# Grill_simple_bord.net
KiCad netlist of a schematic drawn in EAGLE
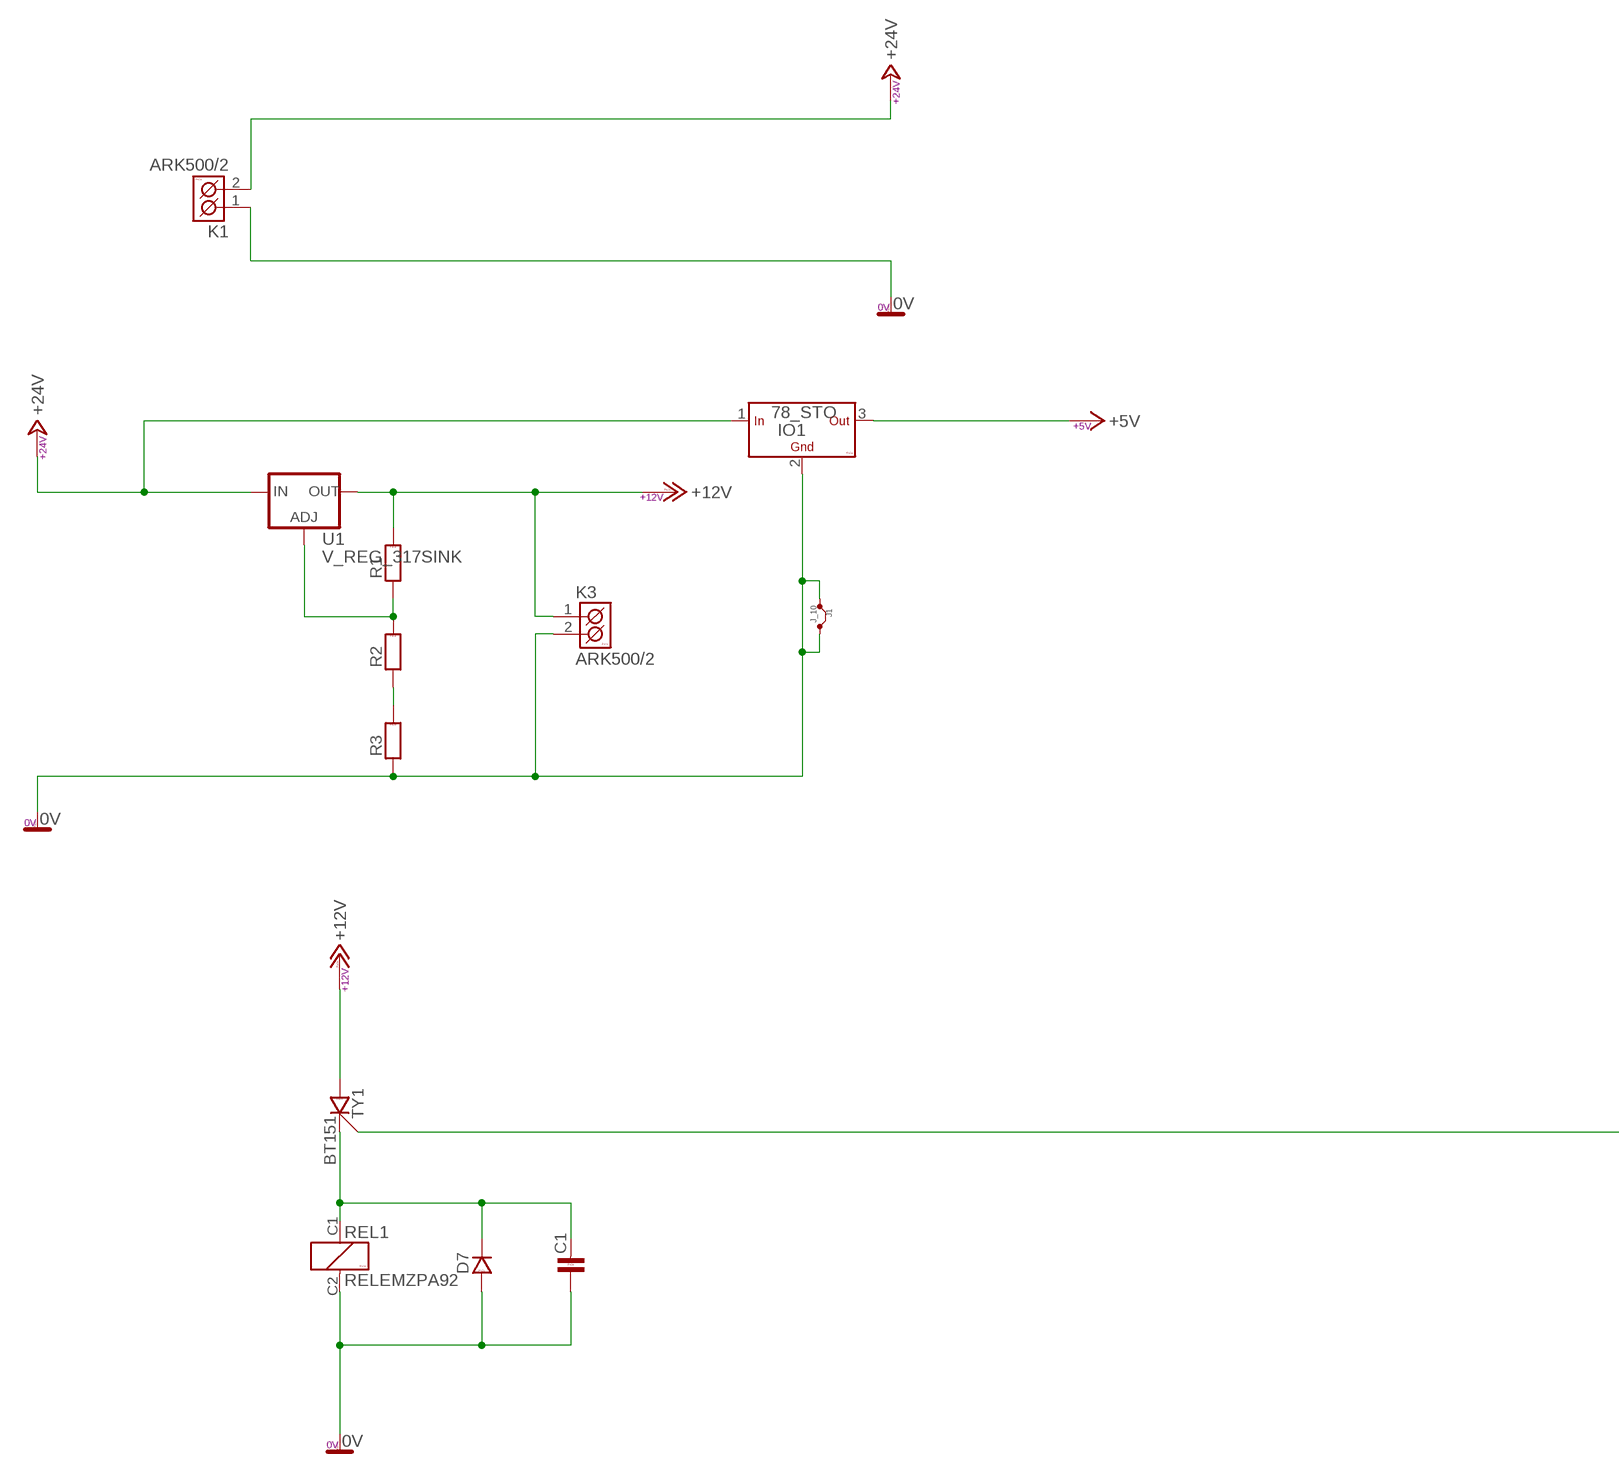
[diagram p0: schematic, sheet 1, part 1 of 2]
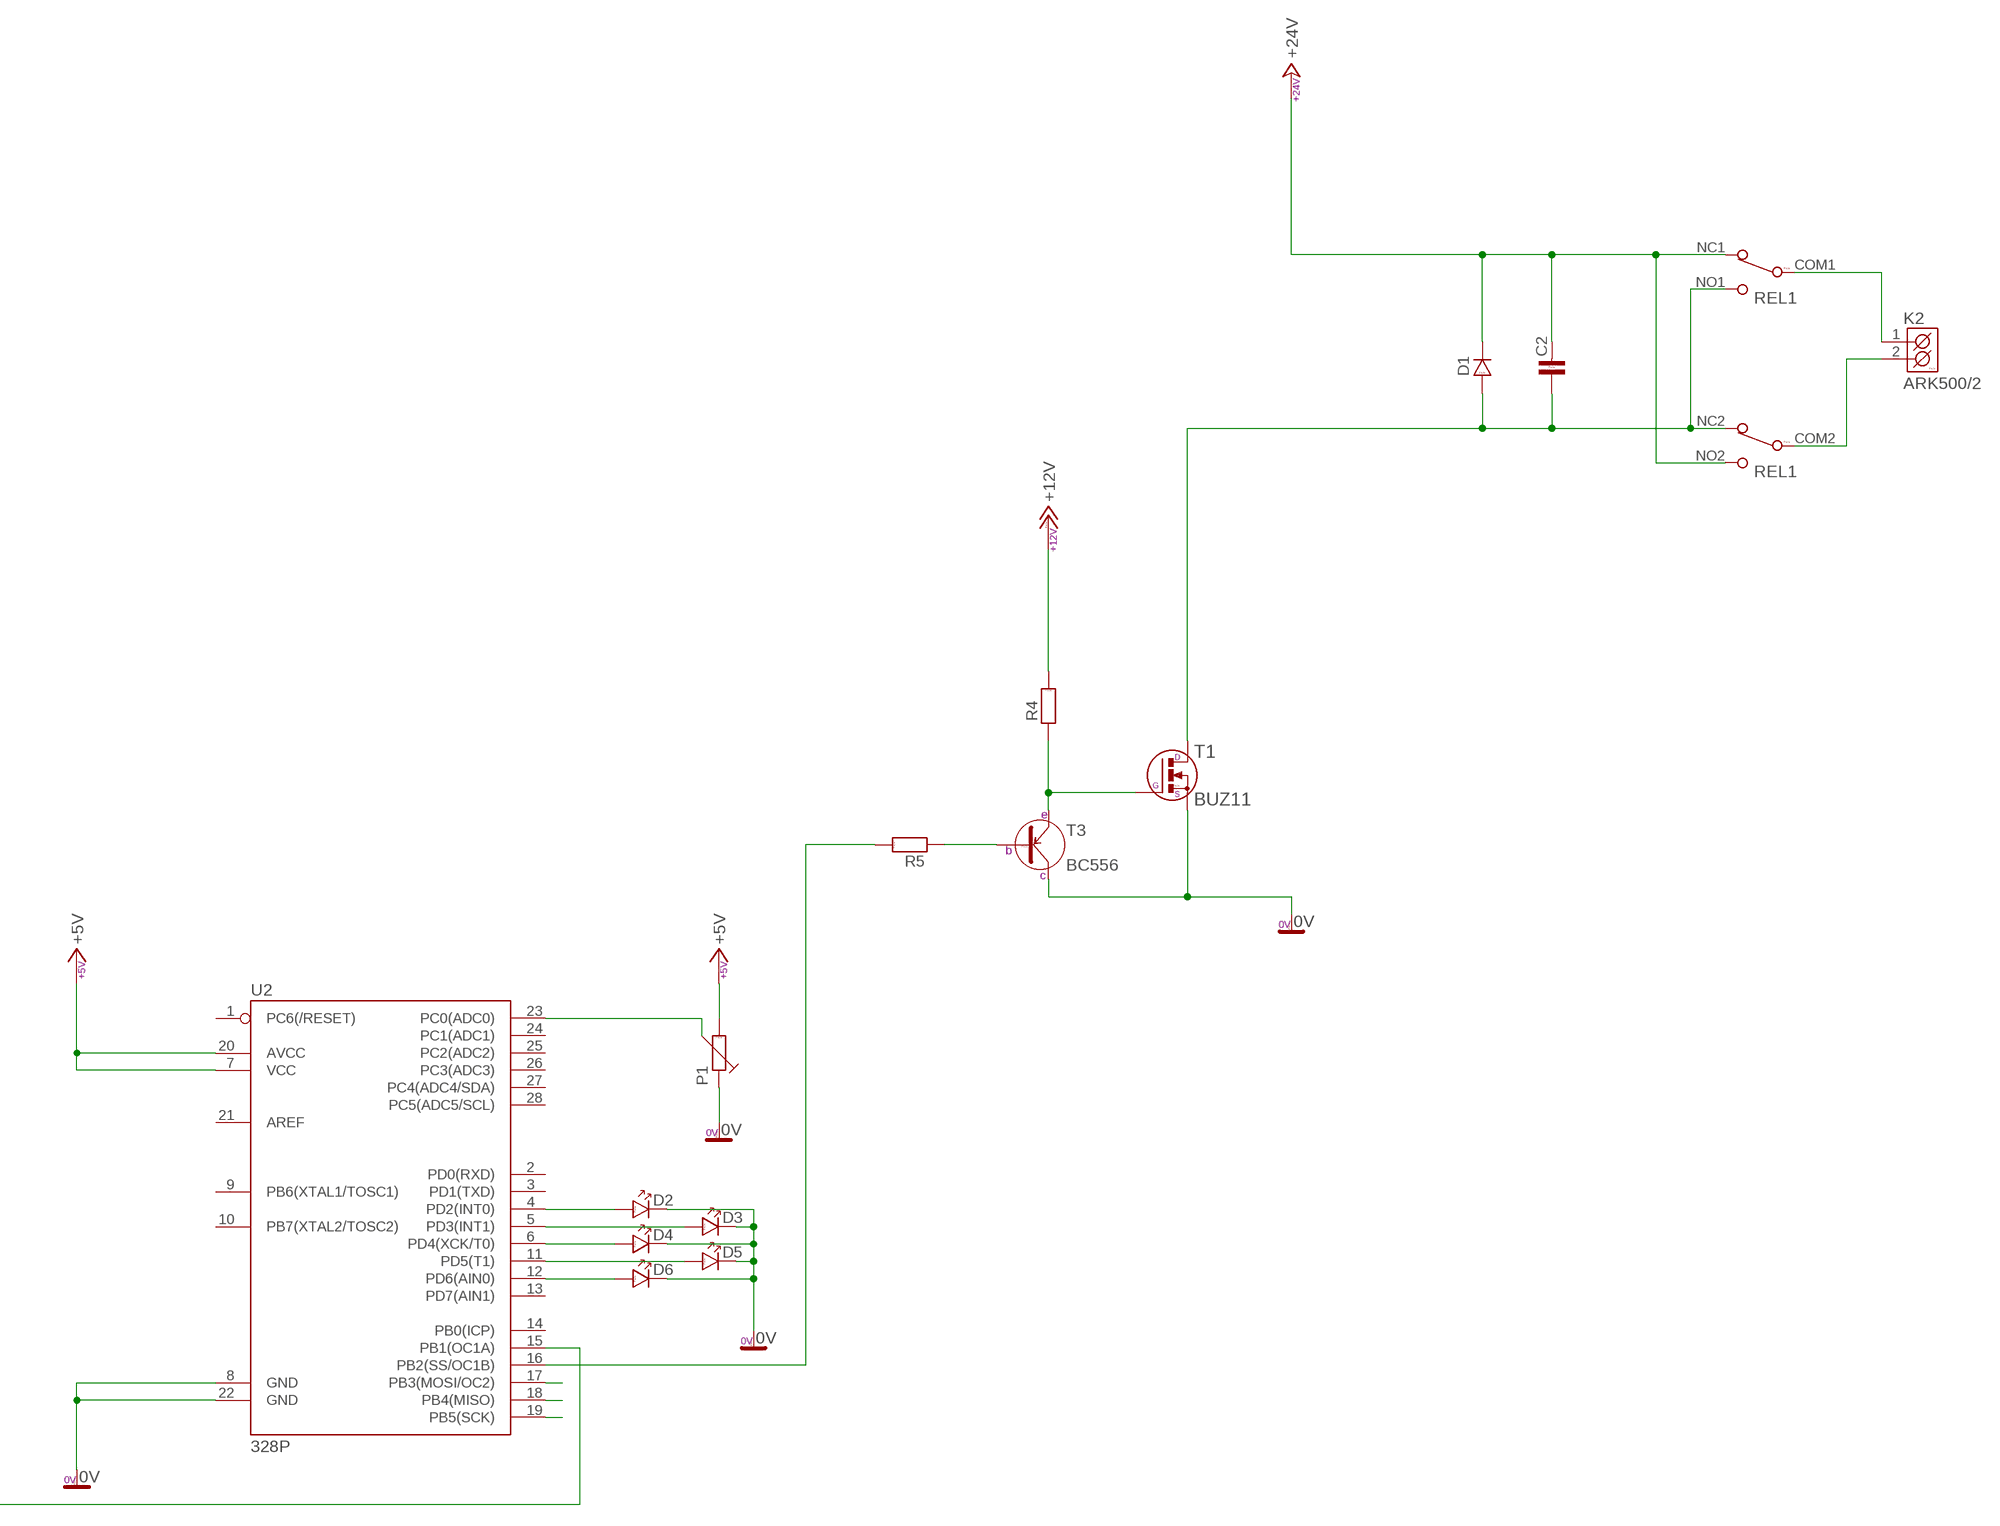
[diagram p1: schematic, sheet 1, part 2 of 2]

(export (version "E")
  (design (tool "Eeschema 10.0.6"))
  (components
    (comp (ref "C1")
      (value "C-KER_5")
      (footprint "eagle-import:C-5")
      (libsource (lib "eagle-import") (part "C-KER_5"))
    )
    (comp (ref "C2")
      (value "C-KER_5")
      (footprint "eagle-import:C-5")
      (libsource (lib "eagle-import") (part "C-KER_5"))
    )
    (comp (ref "D1")
      (value "D_10")
      (footprint "eagle-import:DO41")
      (libsource (lib "eagle-import") (part "D_10"))
    )
    (comp (ref "D2")
      (value "LED_5")
      (footprint "eagle-import:LED_5")
      (libsource (lib "eagle-import") (part "LED_5"))
    )
    (comp (ref "D3")
      (value "LED_5")
      (footprint "eagle-import:LED_5")
      (libsource (lib "eagle-import") (part "LED_5"))
    )
    (comp (ref "D4")
      (value "LED_5")
      (footprint "eagle-import:LED_5")
      (libsource (lib "eagle-import") (part "LED_5"))
    )
    (comp (ref "D5")
      (value "LED_5")
      (footprint "eagle-import:LED_5")
      (libsource (lib "eagle-import") (part "LED_5"))
    )
    (comp (ref "D6")
      (value "LED_5")
      (footprint "eagle-import:LED_5")
      (libsource (lib "eagle-import") (part "LED_5"))
    )
    (comp (ref "D7")
      (value "D_10")
      (footprint "eagle-import:DO41")
      (libsource (lib "eagle-import") (part "D_10"))
    )
    (comp (ref "IO1")
      (value "78_STO")
      (footprint "eagle-import:TO-220S")
      (libsource (lib "eagle-import") (part "78?_STO"))
    )
    (comp (ref "J1")
      (value "J_10")
      (footprint "eagle-import:J_10")
      (libsource (lib "eagle-import") (part "J_10"))
    )
    (comp (ref "K1")
      (value "ARK500/2")
      (footprint "eagle-import:ARK500_2")
      (libsource (lib "eagle-import") (part "ARK500/2"))
    )
    (comp (ref "K2")
      (value "ARK500/2")
      (footprint "eagle-import:ARK500_2")
      (libsource (lib "eagle-import") (part "ARK500/2"))
    )
    (comp (ref "K3")
      (value "ARK500/2")
      (footprint "eagle-import:ARK500_2")
      (libsource (lib "eagle-import") (part "ARK500/2"))
    )
    (comp (ref "P1")
      (value "TRIMRPT6V")
      (footprint "eagle-import:PT6V")
      (libsource (lib "eagle-import") (part "TRIMRPT6V"))
    )
    (comp (ref "R1")
      (value "R_7,5")
      (footprint "eagle-import:R-7,5")
      (libsource (lib "eagle-import") (part "R_7,5"))
    )
    (comp (ref "R2")
      (value "R_7,5")
      (footprint "eagle-import:R-7,5")
      (libsource (lib "eagle-import") (part "R_7,5"))
    )
    (comp (ref "R3")
      (value "R_7,5")
      (footprint "eagle-import:R-7,5")
      (libsource (lib "eagle-import") (part "R_7,5"))
    )
    (comp (ref "R4")
      (value "R_7,5")
      (footprint "eagle-import:R-7,5")
      (libsource (lib "eagle-import") (part "R_7,5"))
    )
    (comp (ref "R5")
      (value "R_7,5")
      (footprint "eagle-import:R-7,5")
      (libsource (lib "eagle-import") (part "R_7,5"))
    )
    (comp (ref "REL1")
      (value "RELEMZPA92")
      (footprint "eagle-import:RELEMZPA92")
      (libsource (lib "eagle-import") (part "RELEMZPA92"))
    )
    (comp (ref "T1")
      (value "BUZ11")
      (footprint "eagle-import:TO-220S")
      (libsource (lib "eagle-import") (part "BUZ11"))
    )
    (comp (ref "T3")
      (value "BC556")
      (footprint "eagle-import:TO-92")
      (libsource (lib "eagle-import") (part "BC556"))
    )
    (comp (ref "TY1")
      (value "BT151")
      (footprint "eagle-import:TO-220S")
      (libsource (lib "eagle-import") (part "BT151"))
    )
    (comp (ref "U1")
      (value "V_REG_317SINK")
      (footprint "eagle-import:TO220-ADJ")
      (libsource (lib "eagle-import") (part "V_REG_317SINK"))
    )
    (comp (ref "U2")
      (value "328P")
      (footprint "eagle-import:DIP28")
      (libsource (lib "eagle-import") (part "ATMEGA328P_PDIP"))
    )
  )
  (nets
    (net (code "1") (name "+5V") (class "Default")
      (node (ref "IO1") (pin "3") (pinfunction "OUT_3") (pintype "passive"))
      (node (ref "P1") (pin "2") (pinfunction "2_2") (pintype "passive"))
      (node (ref "U2") (pin "20") (pinfunction "AVCC_20") (pintype "bidirectional"))
      (node (ref "U2") (pin "7") (pinfunction "VCC_7") (pintype "bidirectional"))
    )
    (net (code "2") (name "+12V") (class "Default")
      (node (ref "K3") (pin "1") (pinfunction "K1_1") (pintype "passive"))
      (node (ref "R1") (pin "2") (pinfunction "2_2") (pintype "passive"))
      (node (ref "R4") (pin "2") (pinfunction "2_2") (pintype "passive"))
      (node (ref "TY1") (pin "2") (pinfunction "A_2") (pintype "passive"))
      (node (ref "U1") (pin "OUT") (pinfunction "OUT_OUT") (pintype "output"))
    )
    (net (code "3") (name "+24V") (class "Default")
      (node (ref "C2") (pin "2") (pinfunction "2_2") (pintype "passive"))
      (node (ref "D1") (pin "K") (pinfunction "K_K") (pintype "passive"))
      (node (ref "IO1") (pin "1") (pinfunction "IN_1") (pintype "passive"))
      (node (ref "K1") (pin "2") (pinfunction "K2_2") (pintype "passive"))
      (node (ref "REL1") (pin "NC1") (pinfunction "NC_NC1") (pintype "passive"))
      (node (ref "REL1") (pin "NO2") (pinfunction "NO_NO2") (pintype "passive"))
      (node (ref "U1") (pin "IN") (pinfunction "IN_IN") (pintype "input"))
    )
    (net (code "4") (name "0V") (class "Default")
      (node (ref "C1") (pin "1") (pinfunction "1_1") (pintype "passive"))
      (node (ref "D2") (pin "K") (pinfunction "K_K") (pintype "passive"))
      (node (ref "D3") (pin "K") (pinfunction "K_K") (pintype "passive"))
      (node (ref "D4") (pin "K") (pinfunction "K_K") (pintype "passive"))
      (node (ref "D5") (pin "K") (pinfunction "K_K") (pintype "passive"))
      (node (ref "D6") (pin "K") (pinfunction "K_K") (pintype "passive"))
      (node (ref "D7") (pin "A") (pinfunction "A_A") (pintype "passive"))
      (node (ref "IO1") (pin "2") (pinfunction "GND_2") (pintype "passive"))
      (node (ref "J1") (pin "P$1") (pinfunction "1_P$1") (pintype "passive"))
      (node (ref "J1") (pin "P$2") (pinfunction "2_P$2") (pintype "passive"))
      (node (ref "K1") (pin "1") (pinfunction "K1_1") (pintype "passive"))
      (node (ref "K3") (pin "2") (pinfunction "K2_2") (pintype "passive"))
      (node (ref "P1") (pin "1") (pinfunction "1_1") (pintype "passive"))
      (node (ref "R3") (pin "1") (pinfunction "1_1") (pintype "passive"))
      (node (ref "REL1") (pin "C2") (pinfunction "C2_C2") (pintype "passive"))
      (node (ref "T1") (pin "3") (pinfunction "S_3") (pintype "passive"))
      (node (ref "T3") (pin "1") (pinfunction "C_1") (pintype "passive"))
      (node (ref "U2") (pin "22") (pinfunction "GND_22") (pintype "bidirectional"))
      (node (ref "U2") (pin "8") (pinfunction "GND_8") (pintype "bidirectional"))
    )
    (net (code "5") (name "Net-(K2-K1)") (class "Default")
      (node (ref "K2") (pin "1") (pinfunction "K1_1") (pintype "passive"))
      (node (ref "REL1") (pin "COM1") (pinfunction "COM_COM1") (pintype "passive"))
    )
    (net (code "6") (name "Net-(K2-K2)") (class "Default")
      (node (ref "K2") (pin "2") (pinfunction "K2_2") (pintype "passive"))
      (node (ref "REL1") (pin "COM2") (pinfunction "COM_COM2") (pintype "passive"))
    )
    (net (code "7") (name "Net-(R1-Pad1)") (class "Default")
      (node (ref "R1") (pin "1") (pinfunction "1_1") (pintype "passive"))
      (node (ref "R2") (pin "2") (pinfunction "2_2") (pintype "passive"))
      (node (ref "U1") (pin "ADJ") (pinfunction "ADJ_ADJ") (pintype "input"))
    )
    (net (code "8") (name "Net-(R2-Pad1)") (class "Default")
      (node (ref "R2") (pin "1") (pinfunction "1_1") (pintype "passive"))
      (node (ref "R3") (pin "2") (pinfunction "2_2") (pintype "passive"))
    )
    (net (code "9") (name "Net-(REL1B-NO)") (class "Default")
      (node (ref "C2") (pin "1") (pinfunction "1_1") (pintype "passive"))
      (node (ref "D1") (pin "A") (pinfunction "A_A") (pintype "passive"))
      (node (ref "REL1") (pin "NC2") (pinfunction "NC_NC2") (pintype "passive"))
      (node (ref "REL1") (pin "NO1") (pinfunction "NO_NO1") (pintype "passive"))
      (node (ref "T1") (pin "2") (pinfunction "D_2") (pintype "passive"))
    )
    (net (code "10") (name "Net-(T1-G)") (class "Default")
      (node (ref "R4") (pin "1") (pinfunction "1_1") (pintype "passive"))
      (node (ref "T1") (pin "1") (pinfunction "G_1") (pintype "passive"))
      (node (ref "T3") (pin "3") (pinfunction "E_3") (pintype "passive"))
    )
    (net (code "11") (name "Net-(T3-B)") (class "Default")
      (node (ref "R5") (pin "1") (pinfunction "1_1") (pintype "passive"))
      (node (ref "T3") (pin "2") (pinfunction "B_2") (pintype "passive"))
    )
    (net (code "12") (name "Net-(TY1-G)") (class "Default")
      (node (ref "TY1") (pin "3") (pinfunction "G_3") (pintype "passive"))
      (node (ref "U2") (pin "15") (pinfunction "PB1(OC1A)_15") (pintype "bidirectional"))
    )
    (net (code "13") (name "Net-(TY1-K)") (class "Default")
      (node (ref "C1") (pin "2") (pinfunction "2_2") (pintype "passive"))
      (node (ref "D7") (pin "K") (pinfunction "K_K") (pintype "passive"))
      (node (ref "REL1") (pin "C1") (pinfunction "C1_C1") (pintype "passive"))
      (node (ref "TY1") (pin "1") (pinfunction "K_1") (pintype "passive"))
    )
    (net (code "14") (name "Net-(U2-PB2(SS{slash}OC1B))") (class "Default")
      (node (ref "R5") (pin "2") (pinfunction "2_2") (pintype "passive"))
      (node (ref "U2") (pin "16") (pinfunction "PB2(SS/OC1B)_16") (pintype "bidirectional"))
    )
    (net (code "15") (name "Net-(U2-PC0(ADC0))") (class "Default")
      (node (ref "P1") (pin "3") (pinfunction "3_3") (pintype "passive"))
      (node (ref "U2") (pin "23") (pinfunction "PC0(ADC0)_23") (pintype "bidirectional"))
    )
    (net (code "16") (name "Net-(U2-PD2(INT0))") (class "Default")
      (node (ref "D2") (pin "A") (pinfunction "A_A") (pintype "passive"))
      (node (ref "U2") (pin "4") (pinfunction "PD2(INT0)_4") (pintype "bidirectional"))
    )
    (net (code "17") (name "Net-(U2-PD3(INT1))") (class "Default")
      (node (ref "D3") (pin "A") (pinfunction "A_A") (pintype "passive"))
      (node (ref "U2") (pin "5") (pinfunction "PD3(INT1)_5") (pintype "bidirectional"))
    )
    (net (code "18") (name "Net-(U2-PD4(XCK{slash}T0))") (class "Default")
      (node (ref "D4") (pin "A") (pinfunction "A_A") (pintype "passive"))
      (node (ref "U2") (pin "6") (pinfunction "PD4(XCK/T0)_6") (pintype "bidirectional"))
    )
    (net (code "19") (name "Net-(U2-PD5(T1))") (class "Default")
      (node (ref "D5") (pin "A") (pinfunction "A_A") (pintype "passive"))
      (node (ref "U2") (pin "11") (pinfunction "PD5(T1)_11") (pintype "bidirectional"))
    )
    (net (code "20") (name "Net-(U2-PD6(AIN0))") (class "Default")
      (node (ref "D6") (pin "A") (pinfunction "A_A") (pintype "passive"))
      (node (ref "U2") (pin "12") (pinfunction "PD6(AIN0)_12") (pintype "bidirectional"))
    )
    (net (code "21") (name "unconnected-(U2-AREF-Pad21)") (class "Default")
      (node (ref "U2") (pin "21") (pinfunction "AREF_21") (pintype "bidirectional"))
    )
    (net (code "22") (name "unconnected-(U2-PB0(ICP)-Pad14)") (class "Default")
      (node (ref "U2") (pin "14") (pinfunction "PB0(ICP)_14") (pintype "bidirectional"))
    )
    (net (code "23") (name "unconnected-(U2-PB3(MOSI{slash}OC2)-Pad17)") (class "Default")
      (node (ref "U2") (pin "17") (pinfunction "PB3(MOSI/OC2)_17") (pintype "bidirectional"))
    )
    (net (code "24") (name "unconnected-(U2-PB4(MISO)-Pad18)") (class "Default")
      (node (ref "U2") (pin "18") (pinfunction "PB4(MISO)_18") (pintype "bidirectional"))
    )
    (net (code "25") (name "unconnected-(U2-PB5(SCK)-Pad19)") (class "Default")
      (node (ref "U2") (pin "19") (pinfunction "PB5(SCK)_19") (pintype "bidirectional"))
    )
    (net (code "26") (name "unconnected-(U2-PB6(XTAL1{slash}TOSC1)-Pad9)") (class "Default")
      (node (ref "U2") (pin "9") (pinfunction "PB6(XTAL1/TOSC1)_9") (pintype "bidirectional"))
    )
    (net (code "27") (name "unconnected-(U2-PB7(XTAL2{slash}TOSC2)-Pad10)") (class "Default")
      (node (ref "U2") (pin "10") (pinfunction "PB7(XTAL2/TOSC2)_10") (pintype "bidirectional"))
    )
    (net (code "28") (name "unconnected-(U2-PC1(ADC1)-Pad24)") (class "Default")
      (node (ref "U2") (pin "24") (pinfunction "PC1(ADC1)_24") (pintype "bidirectional"))
    )
    (net (code "29") (name "unconnected-(U2-PC2(ADC2)-Pad25)") (class "Default")
      (node (ref "U2") (pin "25") (pinfunction "PC2(ADC2)_25") (pintype "bidirectional"))
    )
    (net (code "30") (name "unconnected-(U2-PC3(ADC3)-Pad26)") (class "Default")
      (node (ref "U2") (pin "26") (pinfunction "PC3(ADC3)_26") (pintype "bidirectional"))
    )
    (net (code "31") (name "unconnected-(U2-PC4(ADC4{slash}SDA)-Pad27)") (class "Default")
      (node (ref "U2") (pin "27") (pinfunction "PC4(ADC4/SDA)_27") (pintype "bidirectional"))
    )
    (net (code "32") (name "unconnected-(U2-PC5(ADC5{slash}SCL)-Pad28)") (class "Default")
      (node (ref "U2") (pin "28") (pinfunction "PC5(ADC5/SCL)_28") (pintype "bidirectional"))
    )
    (net (code "33") (name "unconnected-(U2-PC6({slash}RESET)-Pad1)") (class "Default")
      (node (ref "U2") (pin "1") (pinfunction "PC6(/RESET)_1") (pintype "bidirectional"))
    )
    (net (code "34") (name "unconnected-(U2-PD0(RXD)-Pad2)") (class "Default")
      (node (ref "U2") (pin "2") (pinfunction "PD0(RXD)_2") (pintype "bidirectional"))
    )
    (net (code "35") (name "unconnected-(U2-PD1(TXD)-Pad3)") (class "Default")
      (node (ref "U2") (pin "3") (pinfunction "PD1(TXD)_3") (pintype "bidirectional"))
    )
    (net (code "36") (name "unconnected-(U2-PD7(AIN1)-Pad13)") (class "Default")
      (node (ref "U2") (pin "13") (pinfunction "PD7(AIN1)_13") (pintype "bidirectional"))
    )
  )
)
